# IDD_measurement.net
KiCad netlist of a schematic drawn in Altium Designer
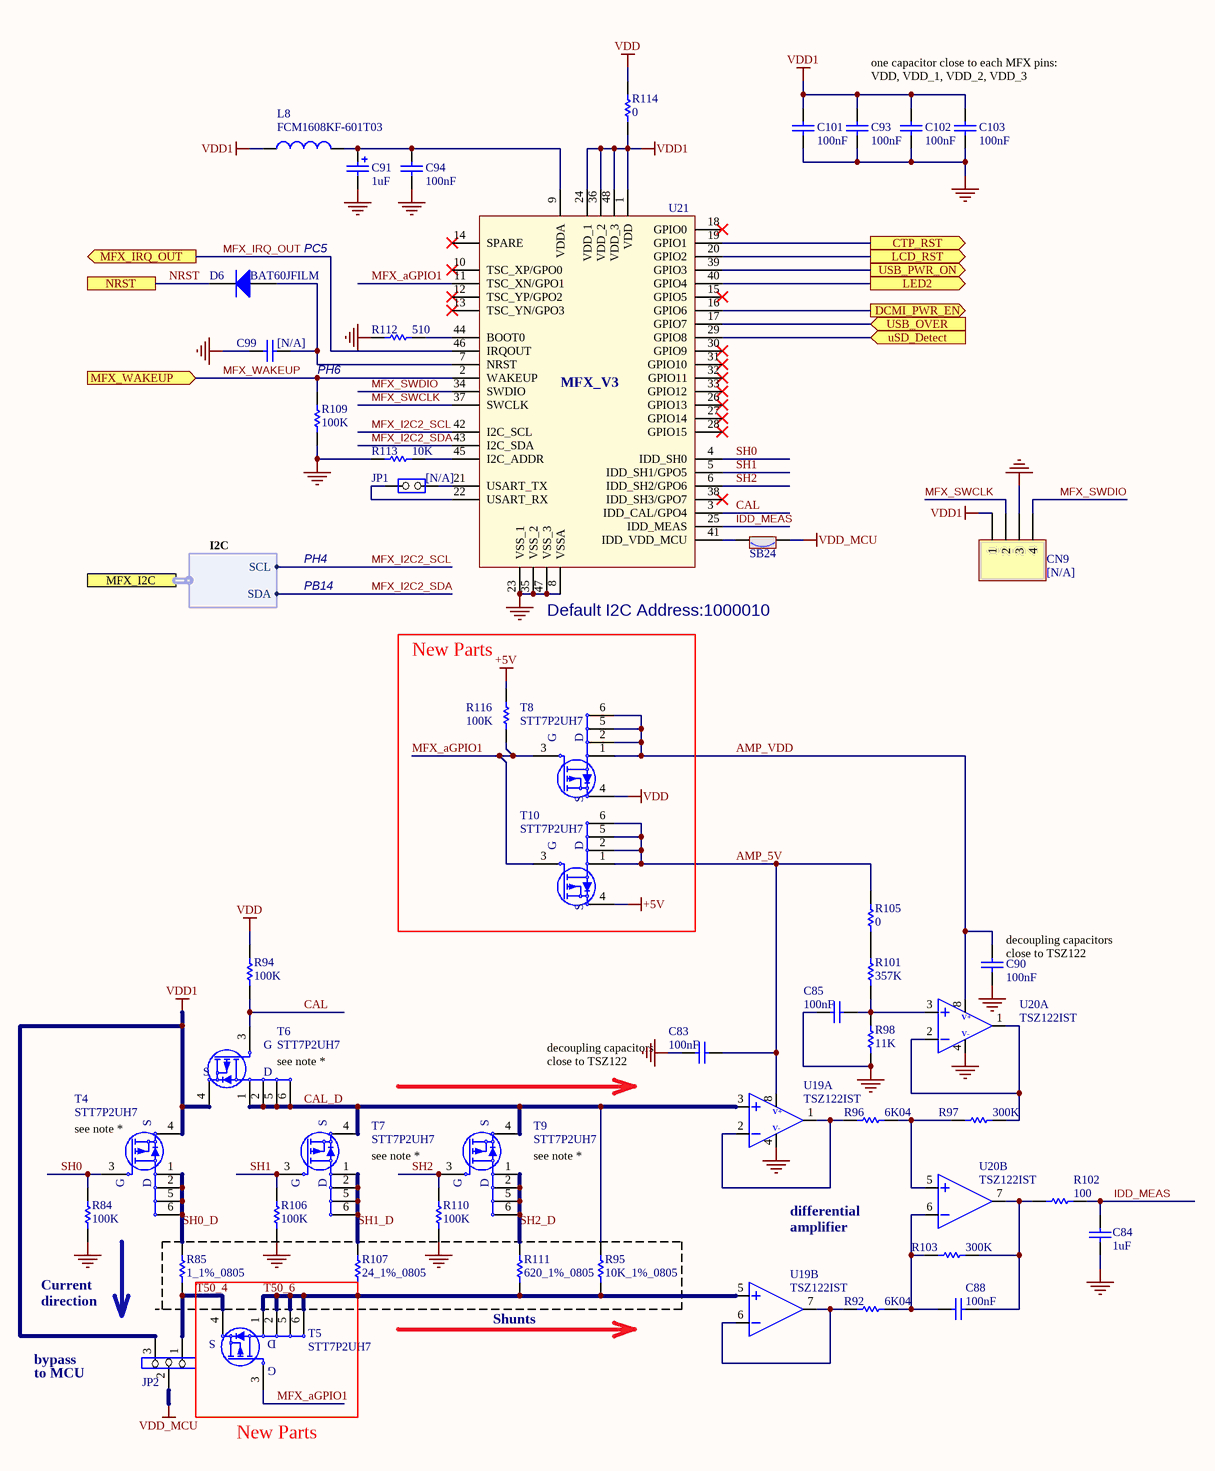
[diagram p0: IDD_measurement.SchDoc]

(export (version "E")
  (design (tool "Eeschema 10.0.6"))
  (components
    (comp (ref "C83")
      (value "100nF")
      (footprint "0603C")
      (description "Capacitor,100nF,10%,16V,X7R,0603,YAGEO")
      (fields (field (name "Comment") "CC0603KRX7R7BB104") (field (name "PUBLISHER") "Altium Limited"))
      (libsource (lib "Miscellaneous Devices") (part "Cap"))
    )
    (comp (ref "C84")
      (value "1uF")
      (footprint "0603C")
      (description "Capacitor,1uF,0603,16V,10%,X5R,YAGEO")
      (fields (field (name "Comment") "CC0603KRX5R7BB105") (field (name "PUBLISHER") "Altium Limited"))
      (libsource (lib "Miscellaneous Devices") (part "Cap"))
    )
    (comp (ref "C85")
      (value "100nF")
      (footprint "0603C")
      (description "Capacitor,100nF,10%,16V,X7R,0603,YAGEO")
      (fields (field (name "Comment") "CC0603KRX7R7BB104") (field (name "PUBLISHER") "Altium Limited"))
      (libsource (lib "Miscellaneous Devices") (part "Cap"))
    )
    (comp (ref "C88")
      (value "100nF")
      (footprint "0603C")
      (description "Capacitor,100nF,10%,16V,X7R,0603,YAGEO")
      (fields (field (name "Comment") "CC0603KRX7R7BB104") (field (name "PUBLISHER") "Altium Limited"))
      (libsource (lib "Miscellaneous Devices") (part "Cap"))
    )
    (comp (ref "C90")
      (value "100nF")
      (footprint "0603C")
      (description "Capacitor,100nF,10%,16V,X7R,0603,YAGEO")
      (fields (field (name "Comment") "CC0603KRX7R7BB104") (field (name "PUBLISHER") "Altium Limited"))
      (libsource (lib "Miscellaneous Devices") (part "Cap"))
    )
    (comp (ref "C91")
      (value "1uF")
      (footprint "TAN-A")
      (description "Tan Capacitor,1uF,10%,16V,Tan-A,TAJA105K016R")
      (fields (field (name "Comment") "TAJA105K016R") (field (name "PUBLISHER") "Altium Limited"))
      (libsource (lib "Miscellaneous Devices") (part "Cap Pol1"))
    )
    (comp (ref "C93")
      (value "100nF")
      (footprint "0603C")
      (description "Capacitor,100nF,10%,16V,X7R,0603,YAGEO")
      (fields (field (name "Comment") "CC0603KRX7R7BB104") (field (name "PUBLISHER") "Altium Limited"))
      (libsource (lib "Miscellaneous Devices") (part "Cap"))
    )
    (comp (ref "C94")
      (value "100nF")
      (footprint "0603C")
      (description "Capacitor,100nF,10%,16V,X7R,0603,YAGEO")
      (fields (field (name "Comment") "CC0603KRX7R7BB104") (field (name "PUBLISHER") "Altium Limited"))
      (libsource (lib "Miscellaneous Devices") (part "Cap"))
    )
    (comp (ref "C99")
      (value "[N/A]")
      (footprint "0603C")
      (description "Capacitor,100nF,10%,16V,X7R,0603,YAGEO")
      (fields (field (name "PUBLISHER") "Altium Limited"))
      (libsource (lib "Miscellaneous Devices") (part "Cap"))
    )
    (comp (ref "C101")
      (value "100nF")
      (footprint "0603C")
      (description "Capacitor,100nF,10%,16V,X7R,0603,YAGEO")
      (fields (field (name "Comment") "CC0603KRX7R7BB104") (field (name "PUBLISHER") "Altium Limited"))
      (libsource (lib "Miscellaneous Devices") (part "Cap"))
    )
    (comp (ref "C102")
      (value "100nF")
      (footprint "0603C")
      (description "Capacitor,100nF,10%,16V,X7R,0603,YAGEO")
      (fields (field (name "Comment") "CC0603KRX7R7BB104") (field (name "PUBLISHER") "Altium Limited"))
      (libsource (lib "Miscellaneous Devices") (part "Cap"))
    )
    (comp (ref "C103")
      (value "100nF")
      (footprint "0603C")
      (description "Capacitor,100nF,10%,16V,X7R,0603,YAGEO")
      (fields (field (name "Comment") "CC0603KRX7R7BB104") (field (name "PUBLISHER") "Altium Limited"))
      (libsource (lib "Miscellaneous Devices") (part "Cap"))
    )
    (comp (ref "CN9")
      (value "[N/A]")
      (footprint "HDR_1X4_2R54")
      (description "Header, 4-Pin")
      (fields (field (name "PUBLISHER") "Altium Limited"))
      (libsource (lib "MCD_TOOLS_CONNECTOR") (part "Header 4"))
    )
    (comp (ref "D6")
      (value "BAT60JFILM")
      (footprint "SOD-323")
      (fields (field (name "PROVIDED") "STM"))
      (libsource (lib "MCD_TOOLS") (part "BAT60JFILM"))
    )
    (comp (ref "JP1")
      (value "[N/A]")
      (footprint "SIP2")
      (description "2 PIN Jumper")
      (libsource (lib "*") (part "JP2"))
    )
    (comp (ref "JP2")
      (value "3 PIN Jumper")
      (footprint "SIP3")
      (description "Jumper 3 pins")
      (libsource (lib "MCD_TOOLS") (part "Jumper3"))
    )
    (comp (ref "L8")
      (value "FCM1608KF-601T03")
      (footprint "0603L")
      (description "Bead,600R,350mA,0603,FCM1608KF-601T03,Tai-tech")
      (libsource (lib "MCD_TOOLS") (part "BEAD_600R_350MA_0603"))
    )
    (comp (ref "R84")
      (value "100K")
      (footprint "0603R")
      (description "Resistor,100K,0603,1%,YAGEO")
      (fields (field (name "Comment") "RC0603FR-07100KL") (field (name "PUBLISHER") "Altium Limited"))
      (libsource (lib "Miscellaneous Devices") (part "res1"))
    )
    (comp (ref "R85")
      (value "1_1%_0805")
      (footprint "0805R")
      (description "Resistor,1,0805,1%,YAGEO")
      (libsource (lib "MCD_TOOLS") (part "Res_1_1%_0805"))
    )
    (comp (ref "R92")
      (value "6K04")
      (footprint "0603R")
      (description "Resistor,6.04K,0603,1%,YAGEO")
      (fields (field (name "Comment") "RC0603FR-076K04L") (field (name "PUBLISHER") "Altium Limited"))
      (libsource (lib "Miscellaneous Devices") (part "res1"))
    )
    (comp (ref "R94")
      (value "100K")
      (footprint "0603R")
      (description "Resistor,100K,0603,1%,YAGEO")
      (fields (field (name "Comment") "RC0603FR-07100KL") (field (name "PUBLISHER") "Altium Limited"))
      (libsource (lib "Miscellaneous Devices") (part "res1"))
    )
    (comp (ref "R95")
      (value "10K_1%_0805")
      (footprint "0805R")
      (description "Resistor,10K,0805,1%,YAGEO")
      (libsource (lib "MCD_TOOLS") (part "Res_10K_1%_0805"))
    )
    (comp (ref "R96")
      (value "6K04")
      (footprint "0603R")
      (description "Resistor,6.04K,0603,1%,YAGEO")
      (fields (field (name "Comment") "RC0603FR-076K04L") (field (name "PUBLISHER") "Altium Limited"))
      (libsource (lib "Miscellaneous Devices") (part "res1"))
    )
    (comp (ref "R97")
      (value "300K")
      (footprint "0603R")
      (description "Resistor,300K,0603,1%,YAGEO")
      (fields (field (name "Comment") "RC0603FR-07300KL") (field (name "PUBLISHER") "Altium Limited"))
      (libsource (lib "Miscellaneous Devices") (part "res1"))
    )
    (comp (ref "R98")
      (value "11K")
      (footprint "0603R")
      (description "Resistor,11K,0603,1%,YAGEO")
      (fields (field (name "Comment") "RC0603FR-0711KL") (field (name "PUBLISHER") "Altium Limited"))
      (libsource (lib "Miscellaneous Devices") (part "res1"))
    )
    (comp (ref "R101")
      (value "357K")
      (footprint "0603R")
      (description "Resistor,357K,0603,1%,YAGEO")
      (fields (field (name "Comment") "RC0603FR-07357KL") (field (name "PUBLISHER") "Altium Limited"))
      (libsource (lib "Miscellaneous Devices") (part "res1"))
    )
    (comp (ref "R102")
      (value "100")
      (footprint "0603R")
      (description "Resistor, 100 ,0603,1%,YAGEO")
      (fields (field (name "Comment") "RC0603JR-07100RL") (field (name "PUBLISHER") "Altium Limited"))
      (libsource (lib "Miscellaneous Devices") (part "res1"))
    )
    (comp (ref "R103")
      (value "300K")
      (footprint "0603R")
      (description "Resistor,300K,0603,1%,YAGEO")
      (fields (field (name "Comment") "RC0603FR-07300KL") (field (name "PUBLISHER") "Altium Limited"))
      (libsource (lib "Miscellaneous Devices") (part "res1"))
    )
    (comp (ref "R105")
      (value "0")
      (footprint "0603R")
      (description "Resistor, 0 ,0603,1%,YAGEO")
      (fields (field (name "Comment") "RC0603JR-070RL") (field (name "PUBLISHER") "Altium Limited"))
      (libsource (lib "Miscellaneous Devices") (part "res1"))
    )
    (comp (ref "R106")
      (value "100K")
      (footprint "0603R")
      (description "Resistor,100K,0603,1%,YAGEO")
      (fields (field (name "Comment") "RC0603FR-07100KL") (field (name "PUBLISHER") "Altium Limited"))
      (libsource (lib "Miscellaneous Devices") (part "res1"))
    )
    (comp (ref "R107")
      (value "24_1%_0805")
      (footprint "0805R")
      (description "Resistor,24,0805,1%,YAGEO")
      (libsource (lib "MCD_TOOLS") (part "Res_24_1%_0805"))
    )
    (comp (ref "R109")
      (value "100K")
      (footprint "0603R")
      (description "Resistor,100K,0603,1%,YAGEO")
      (fields (field (name "Comment") "RC0603FR-07100KL") (field (name "PUBLISHER") "Altium Limited"))
      (libsource (lib "Miscellaneous Devices") (part "res1"))
    )
    (comp (ref "R110")
      (value "100K")
      (footprint "0603R")
      (description "Resistor,100K,0603,1%,YAGEO")
      (fields (field (name "Comment") "RC0603FR-07100KL") (field (name "PUBLISHER") "Altium Limited"))
      (libsource (lib "Miscellaneous Devices") (part "res1"))
    )
    (comp (ref "R111")
      (value "620_1%_0805")
      (footprint "0805R")
      (description "Resistor,620,0805,1%,YAGEO")
      (libsource (lib "MCD_TOOLS") (part "Res_620_1%_0805"))
    )
    (comp (ref "R112")
      (value "510")
      (footprint "0603R")
      (description "Resistor,510R,0603,1%,YAGEO")
      (fields (field (name "Comment") "RC0603FR-07510RL") (field (name "PUBLISHER") "Altium Limited"))
      (libsource (lib "Miscellaneous Devices") (part "res1"))
    )
    (comp (ref "R113")
      (value "10K")
      (footprint "0603R")
      (description "Resistor,10K,0603,1%,YAGEO")
      (fields (field (name "Comment") "RC0603FR-0710KL") (field (name "PUBLISHER") "Altium Limited"))
      (libsource (lib "Miscellaneous Devices") (part "res1"))
    )
    (comp (ref "R114")
      (value "0")
      (footprint "0603R")
      (description "Resistor, 0 ,0603,1%,YAGEO")
      (fields (field (name "Comment") "RC0603JR-070RL") (field (name "PUBLISHER") "Altium Limited"))
      (libsource (lib "Miscellaneous Devices") (part "res1"))
    )
    (comp (ref "R116")
      (value "100K")
      (footprint "0603R")
      (description "Resistor,100K,0603,1%,YAGEO")
      (fields (field (name "Comment") "RC0603FR-07100KL") (field (name "PUBLISHER") "Altium Limited"))
      (libsource (lib "Miscellaneous Devices") (part "res1"))
    )
    (comp (ref "SB24")
      (value "Solder Bridge ON")
      (footprint "SB_0603")
      (libsource (lib "MCD_TOOLS") (part "SB_ON"))
    )
    (comp (ref "T4")
      (value "STT7P2UH7")
      (footprint "SOT23-6L")
      (description "STripFET VII DeepGATE Power MOSFET, P-CHANNEL 20 V, 0.0146, 7 A - SOT23-6L")
      (libsource (lib "MCD_TOOLS") (part "STT7P2UH7"))
    )
    (comp (ref "T5")
      (value "STT7P2UH7")
      (footprint "SOT23-6L")
      (description "STripFET VII DeepGATE Power MOSFET, P-CHANNEL 20 V, 0.0146, 7 A - SOT23-6L")
      (libsource (lib "MCD_TOOLS") (part "STT7P2UH7"))
    )
    (comp (ref "T6")
      (value "STT7P2UH7")
      (footprint "SOT23-6L")
      (description "STripFET VII DeepGATE Power MOSFET, P-CHANNEL 20 V, 0.0146, 7 A - SOT23-6L")
      (libsource (lib "MCD_TOOLS") (part "STT7P2UH7"))
    )
    (comp (ref "T7")
      (value "STT7P2UH7")
      (footprint "SOT23-6L")
      (description "STripFET VII DeepGATE Power MOSFET, P-CHANNEL 20 V, 0.0146, 7 A - SOT23-6L")
      (libsource (lib "MCD_TOOLS") (part "STT7P2UH7"))
    )
    (comp (ref "T8")
      (value "STT7P2UH7")
      (footprint "SOT23-6L")
      (description "STripFET VII DeepGATE Power MOSFET, P-CHANNEL 20 V, 0.0146, 7 A - SOT23-6L")
      (libsource (lib "MCD_TOOLS") (part "STT7P2UH7"))
    )
    (comp (ref "T9")
      (value "STT7P2UH7")
      (footprint "SOT23-6L")
      (description "STripFET VII DeepGATE Power MOSFET, P-CHANNEL 20 V, 0.0146, 7 A - SOT23-6L")
      (libsource (lib "MCD_TOOLS") (part "STT7P2UH7"))
    )
    (comp (ref "T10")
      (value "STT7P2UH7")
      (footprint "SOT23-6L")
      (description "STripFET VII DeepGATE Power MOSFET, P-CHANNEL 20 V, 0.0146, 7 A - SOT23-6L")
      (libsource (lib "MCD_TOOLS") (part "STT7P2UH7"))
    )
    (comp (ref "U19")
      (value "TSZ122IST")
      (footprint "miniSO8")
      (description "Very high accuracy (5 礦) zero drift 5 V dual OpAmp")
      (libsource (lib "MCD_TOOLS") (part "TSZ122IST"))
    )
    (comp (ref "U20")
      (value "TSZ122IST")
      (footprint "miniSO8")
      (description "Very high accuracy (5 礦) zero drift 5 V dual OpAmp")
      (libsource (lib "MCD_TOOLS") (part "TSZ122IST"))
    )
    (comp (ref "U21")
      (value "STM32L152CCT6")
      (footprint "LQFP48_0R5_9X9")
      (description "Multifunction expander")
      (libsource (lib "MB1167") (part "MFX"))
    )
  )
  (nets
    (net (code "2") (name "+5V") (class "Default")
      (node (ref "R116") (pin "2") (pinfunction "2_2") (pintype "passive"))
      (node (ref "T10") (pin "4") (pinfunction "S_4") (pintype "passive"))
    )
    (net (code "3") (name "/AMP_5V") (class "Default")
      (node (ref "C83") (pin "2") (pinfunction "2_2") (pintype "passive"))
      (node (ref "R105") (pin "2") (pinfunction "2_2") (pintype "passive"))
      (node (ref "T10") (pin "1") (pinfunction "S_1") (pintype "passive"))
      (node (ref "T10") (pin "2") (pinfunction "S_2") (pintype "passive"))
      (node (ref "T10") (pin "5") (pinfunction "D_5") (pintype "passive"))
      (node (ref "T10") (pin "6") (pinfunction "D_6") (pintype "passive"))
      (node (ref "U19") (pin "8") (pintype "passive"))
    )
    (net (code "4") (name "/AMP_VDD") (class "Default")
      (node (ref "C90") (pin "1") (pinfunction "1_1") (pintype "passive"))
      (node (ref "T8") (pin "1") (pinfunction "S_1") (pintype "passive"))
      (node (ref "T8") (pin "2") (pinfunction "S_2") (pintype "passive"))
      (node (ref "T8") (pin "5") (pinfunction "D_5") (pintype "passive"))
      (node (ref "T8") (pin "6") (pinfunction "D_6") (pintype "passive"))
      (node (ref "U20") (pin "8") (pintype "passive"))
    )
    (net (code "5") (name "/CAL") (class "Default")
      (node (ref "R94") (pin "1") (pinfunction "1_1") (pintype "passive"))
      (node (ref "T6") (pin "3") (pinfunction "G_3") (pintype "passive"))
      (node (ref "U21") (pin "3") (pinfunction "IDD_CAL/GPO4_3") (pintype "passive"))
    )
    (net (code "6") (name "/CAL_D") (class "Default")
      (node (ref "R95") (pin "2") (pinfunction "2_2") (pintype "passive"))
      (node (ref "T6") (pin "1") (pinfunction "S_1") (pintype "passive"))
      (node (ref "T6") (pin "2") (pinfunction "S_2") (pintype "passive"))
      (node (ref "T6") (pin "5") (pinfunction "D_5") (pintype "passive"))
      (node (ref "T6") (pin "6") (pinfunction "D_6") (pintype "passive"))
      (node (ref "T7") (pin "4") (pinfunction "S_4") (pintype "passive"))
      (node (ref "T9") (pin "4") (pinfunction "S_4") (pintype "passive"))
      (node (ref "U19") (pin "3") (pintype "passive"))
    )
    (net (code "7") (name "/CTP_RST") (class "Default")
      (node (ref "U21") (pin "19") (pinfunction "GPIO1_19") (pintype "passive"))
    )
    (net (code "8") (name "/DCMI_PWR_EN") (class "Default")
      (node (ref "U21") (pin "16") (pinfunction "GPIO6_16") (pintype "passive"))
    )
    (net (code "9") (name "/IDD_MEAS") (class "Default")
      (node (ref "C84") (pin "1") (pinfunction "1_1") (pintype "passive"))
      (node (ref "R102") (pin "1") (pinfunction "1_1") (pintype "passive"))
      (node (ref "U21") (pin "25") (pinfunction "IDD_MEAS_25") (pintype "passive"))
    )
    (net (code "10") (name "/LCD_RST") (class "Default")
      (node (ref "U21") (pin "20") (pinfunction "GPIO2_20") (pintype "passive"))
    )
    (net (code "11") (name "/LED2") (class "Default")
      (node (ref "U21") (pin "40") (pinfunction "GPIO4_40") (pintype "passive"))
    )
    (net (code "12") (name "/MFX_I2C2_SCL") (class "Default")
      (node (ref "U21") (pin "42") (pinfunction "I2C_SCL_42") (pintype "passive"))
    )
    (net (code "13") (name "/MFX_I2C2_SDA") (class "Default")
      (node (ref "U21") (pin "43") (pinfunction "I2C_SDA_43") (pintype "passive"))
    )
    (net (code "14") (name "/MFX_IRQ_OUT") (class "Default")
      (node (ref "U21") (pin "46") (pinfunction "IRQOUT_46") (pintype "passive"))
    )
    (net (code "15") (name "/MFX_SWCLK") (class "Default")
      (node (ref "CN9") (pin "2") (pinfunction "2_2") (pintype "passive"))
      (node (ref "U21") (pin "37") (pinfunction "SWCLK_37") (pintype "passive"))
    )
    (net (code "16") (name "/MFX_SWDIO") (class "Default")
      (node (ref "CN9") (pin "4") (pinfunction "4_4") (pintype "passive"))
      (node (ref "U21") (pin "34") (pinfunction "SWDIO_34") (pintype "passive"))
    )
    (net (code "17") (name "/MFX_WAKEUP") (class "Default")
      (node (ref "R109") (pin "2") (pinfunction "2_2") (pintype "passive"))
      (node (ref "U21") (pin "2") (pinfunction "WAKEUP_2") (pintype "passive"))
    )
    (net (code "18") (name "/MFX_aGPIO1") (class "Default")
      (node (ref "R116") (pin "1") (pinfunction "1_1") (pintype "passive"))
      (node (ref "T10") (pin "3") (pinfunction "G_3") (pintype "passive"))
      (node (ref "T5") (pin "3") (pinfunction "G_3") (pintype "passive"))
      (node (ref "T8") (pin "3") (pinfunction "G_3") (pintype "passive"))
      (node (ref "U21") (pin "11") (pinfunction "TSC_XN/GPO1_11") (pintype "passive"))
    )
    (net (code "19") (name "/NRST") (class "Default")
      (node (ref "D6") (pin "2") (pinfunction "K_2") (pintype "passive"))
    )
    (net (code "20") (name "/SH0") (class "Default")
      (node (ref "R84") (pin "2") (pinfunction "2_2") (pintype "passive"))
      (node (ref "T4") (pin "3") (pinfunction "G_3") (pintype "passive"))
      (node (ref "U21") (pin "4") (pinfunction "IDD_SH0_4") (pintype "passive"))
    )
    (net (code "21") (name "/SH0_D") (class "Default")
      (node (ref "R85") (pin "2") (pinfunction "2_2") (pintype "passive"))
      (node (ref "T4") (pin "1") (pinfunction "S_1") (pintype "passive"))
      (node (ref "T4") (pin "2") (pinfunction "S_2") (pintype "passive"))
      (node (ref "T4") (pin "5") (pinfunction "D_5") (pintype "passive"))
      (node (ref "T4") (pin "6") (pinfunction "D_6") (pintype "passive"))
    )
    (net (code "22") (name "/SH1") (class "Default")
      (node (ref "R106") (pin "2") (pinfunction "2_2") (pintype "passive"))
      (node (ref "T7") (pin "3") (pinfunction "G_3") (pintype "passive"))
      (node (ref "U21") (pin "5") (pinfunction "IDD_SH1/GPO5_5") (pintype "passive"))
    )
    (net (code "23") (name "/SH1_D") (class "Default")
      (node (ref "R107") (pin "2") (pinfunction "2_2") (pintype "passive"))
      (node (ref "T7") (pin "1") (pinfunction "S_1") (pintype "passive"))
      (node (ref "T7") (pin "2") (pinfunction "S_2") (pintype "passive"))
      (node (ref "T7") (pin "5") (pinfunction "D_5") (pintype "passive"))
      (node (ref "T7") (pin "6") (pinfunction "D_6") (pintype "passive"))
    )
    (net (code "24") (name "/SH2") (class "Default")
      (node (ref "R110") (pin "2") (pinfunction "2_2") (pintype "passive"))
      (node (ref "T9") (pin "3") (pinfunction "G_3") (pintype "passive"))
      (node (ref "U21") (pin "6") (pinfunction "IDD_SH2/GPO6_6") (pintype "passive"))
    )
    (net (code "25") (name "/SH2_D") (class "Default")
      (node (ref "R111") (pin "2") (pinfunction "2_2") (pintype "passive"))
      (node (ref "T9") (pin "1") (pinfunction "S_1") (pintype "passive"))
      (node (ref "T9") (pin "2") (pinfunction "S_2") (pintype "passive"))
      (node (ref "T9") (pin "5") (pinfunction "D_5") (pintype "passive"))
      (node (ref "T9") (pin "6") (pinfunction "D_6") (pintype "passive"))
    )
    (net (code "26") (name "/T50_4") (class "Default")
      (node (ref "JP2") (pin "1") (pintype "passive"))
      (node (ref "R85") (pin "1") (pinfunction "1_1") (pintype "passive"))
      (node (ref "T5") (pin "4") (pinfunction "S_4") (pintype "passive"))
    )
    (net (code "27") (name "/T50_6") (class "Default")
      (node (ref "R107") (pin "1") (pinfunction "1_1") (pintype "passive"))
      (node (ref "R111") (pin "1") (pinfunction "1_1") (pintype "passive"))
      (node (ref "R95") (pin "1") (pinfunction "1_1") (pintype "passive"))
      (node (ref "T5") (pin "1") (pinfunction "S_1") (pintype "passive"))
      (node (ref "T5") (pin "2") (pinfunction "S_2") (pintype "passive"))
      (node (ref "T5") (pin "5") (pinfunction "D_5") (pintype "passive"))
      (node (ref "T5") (pin "6") (pinfunction "D_6") (pintype "passive"))
      (node (ref "U19") (pin "5") (pintype "passive"))
    )
    (net (code "28") (name "/USB_OVER") (class "Default")
      (node (ref "U21") (pin "17") (pinfunction "GPIO7_17") (pintype "passive"))
    )
    (net (code "29") (name "/USB_PWR_ON") (class "Default")
      (node (ref "U21") (pin "39") (pinfunction "GPIO3_39") (pintype "passive"))
    )
    (net (code "30") (name "/uSD_Detect") (class "Default")
      (node (ref "U21") (pin "29") (pinfunction "GPIO8_29") (pintype "passive"))
    )
    (net (code "32") (name "GND") (class "Default")
      (node (ref "C101") (pin "2") (pinfunction "2_2") (pintype "passive"))
      (node (ref "C102") (pin "2") (pinfunction "2_2") (pintype "passive"))
      (node (ref "C103") (pin "2") (pinfunction "2_2") (pintype "passive"))
      (node (ref "C83") (pin "1") (pinfunction "1_1") (pintype "passive"))
      (node (ref "C84") (pin "2") (pinfunction "2_2") (pintype "passive"))
      (node (ref "C85") (pin "1") (pinfunction "1_1") (pintype "passive"))
      (node (ref "C90") (pin "2") (pinfunction "2_2") (pintype "passive"))
      (node (ref "C91") (pin "2") (pinfunction "2_2") (pintype "passive"))
      (node (ref "C93") (pin "2") (pinfunction "2_2") (pintype "passive"))
      (node (ref "C94") (pin "2") (pinfunction "2_2") (pintype "passive"))
      (node (ref "C99") (pin "1") (pinfunction "1_1") (pintype "passive"))
      (node (ref "CN9") (pin "3") (pinfunction "3_3") (pintype "passive"))
      (node (ref "R106") (pin "1") (pinfunction "1_1") (pintype "passive"))
      (node (ref "R109") (pin "1") (pinfunction "1_1") (pintype "passive"))
      (node (ref "R110") (pin "1") (pinfunction "1_1") (pintype "passive"))
      (node (ref "R112") (pin "2") (pinfunction "2_2") (pintype "passive"))
      (node (ref "R113") (pin "2") (pinfunction "2_2") (pintype "passive"))
      (node (ref "R84") (pin "1") (pinfunction "1_1") (pintype "passive"))
      (node (ref "R98") (pin "2") (pinfunction "2_2") (pintype "passive"))
      (node (ref "U19") (pin "4") (pintype "passive"))
      (node (ref "U20") (pin "4") (pintype "passive"))
      (node (ref "U21") (pin "23") (pinfunction "VSS_1_23") (pintype "passive"))
      (node (ref "U21") (pin "35") (pinfunction "VSS_2_35") (pintype "passive"))
      (node (ref "U21") (pin "47") (pinfunction "VSS_3_47") (pintype "passive"))
      (node (ref "U21") (pin "8") (pinfunction "VSSA_8") (pintype "passive"))
    )
    (net (code "33") (name "Net-(C85-Pad2)") (class "Default")
      (node (ref "C85") (pin "2") (pinfunction "2_2") (pintype "passive"))
      (node (ref "R101") (pin "2") (pinfunction "2_2") (pintype "passive"))
      (node (ref "R98") (pin "1") (pinfunction "1_1") (pintype "passive"))
      (node (ref "U20") (pin "3") (pintype "passive"))
    )
    (net (code "34") (name "Net-(C88-Pad1)") (class "Default")
      (node (ref "C88") (pin "1") (pinfunction "1_1") (pintype "passive"))
      (node (ref "R103") (pin "1") (pinfunction "1_1") (pintype "passive"))
      (node (ref "R92") (pin "1") (pinfunction "1_1") (pintype "passive"))
      (node (ref "U20") (pin "6") (pintype "passive"))
    )
    (net (code "35") (name "Net-(C88-Pad2)") (class "Default")
      (node (ref "C88") (pin "2") (pinfunction "2_2") (pintype "passive"))
      (node (ref "R102") (pin "2") (pinfunction "2_2") (pintype "passive"))
      (node (ref "R103") (pin "2") (pinfunction "2_2") (pintype "passive"))
      (node (ref "U20") (pin "7") (pintype "passive"))
    )
    (net (code "36") (name "Net-(D6-A)") (class "Default")
      (node (ref "C99") (pin "2") (pinfunction "2_2") (pintype "passive"))
      (node (ref "D6") (pin "1") (pinfunction "A_1") (pintype "passive"))
      (node (ref "U21") (pin "7") (pinfunction "NRST_7") (pintype "passive"))
    )
    (net (code "37") (name "Net-(JP1-COMMON)") (class "Default")
      (node (ref "JP1") (pin "1") (pinfunction "COMMON_1") (pintype "passive"))
      (node (ref "U21") (pin "22") (pinfunction "USART_RX_22") (pintype "passive"))
    )
    (net (code "38") (name "Net-(JP1-NO)") (class "Default")
      (node (ref "JP1") (pin "2") (pinfunction "NO_2") (pintype "passive"))
      (node (ref "U21") (pin "21") (pinfunction "USART_TX_21") (pintype "passive"))
    )
    (net (code "39") (name "Net-(R92-Pad2)") (class "Default")
      (node (ref "R92") (pin "2") (pinfunction "2_2") (pintype "passive"))
      (node (ref "U19") (pin "6") (pintype "passive"))
      (node (ref "U19") (pin "7") (pintype "passive"))
    )
    (net (code "40") (name "Net-(R96-Pad1)") (class "Default")
      (node (ref "R96") (pin "1") (pinfunction "1_1") (pintype "passive"))
      (node (ref "R97") (pin "1") (pinfunction "1_1") (pintype "passive"))
      (node (ref "U20") (pin "5") (pintype "passive"))
    )
    (net (code "41") (name "Net-(R96-Pad2)") (class "Default")
      (node (ref "R96") (pin "2") (pinfunction "2_2") (pintype "passive"))
      (node (ref "U19") (pin "1") (pintype "passive"))
      (node (ref "U19") (pin "2") (pintype "passive"))
    )
    (net (code "42") (name "Net-(R97-Pad2)") (class "Default")
      (node (ref "R97") (pin "2") (pinfunction "2_2") (pintype "passive"))
      (node (ref "U20") (pin "1") (pintype "passive"))
      (node (ref "U20") (pin "2") (pintype "passive"))
    )
    (net (code "43") (name "Net-(R101-Pad1)") (class "Default")
      (node (ref "R101") (pin "1") (pinfunction "1_1") (pintype "passive"))
      (node (ref "R105") (pin "1") (pinfunction "1_1") (pintype "passive"))
    )
    (net (code "44") (name "Net-(U21-BOOT0)") (class "Default")
      (node (ref "R112") (pin "1") (pinfunction "1_1") (pintype "passive"))
      (node (ref "U21") (pin "44") (pinfunction "BOOT0_44") (pintype "passive"))
    )
    (net (code "45") (name "Net-(U21-I2C_ADDR)") (class "Default")
      (node (ref "R113") (pin "1") (pinfunction "1_1") (pintype "passive"))
      (node (ref "U21") (pin "45") (pinfunction "I2C_ADDR_45") (pintype "passive"))
    )
    (net (code "46") (name "Net-(U21-IDD_VDD_MCU)") (class "Default")
      (node (ref "SB24") (pin "2") (pinfunction "2_2") (pintype "passive"))
      (node (ref "U21") (pin "41") (pinfunction "IDD_VDD_MCU_41") (pintype "passive"))
    )
    (net (code "47") (name "Net-(U21-VDDA)") (class "Default")
      (node (ref "C91") (pin "1") (pinfunction "1_1") (pintype "passive"))
      (node (ref "C94") (pin "1") (pinfunction "1_1") (pintype "passive"))
      (node (ref "L8") (pin "2") (pinfunction "2_2") (pintype "passive"))
      (node (ref "U21") (pin "9") (pinfunction "VDDA_9") (pintype "passive"))
    )
    (net (code "48") (name "VDD") (class "Default")
      (node (ref "R114") (pin "1") (pinfunction "1_1") (pintype "passive"))
      (node (ref "R94") (pin "2") (pinfunction "2_2") (pintype "passive"))
      (node (ref "T8") (pin "4") (pinfunction "S_4") (pintype "passive"))
    )
    (net (code "49") (name "VDD1") (class "Default")
      (node (ref "C101") (pin "1") (pinfunction "1_1") (pintype "passive"))
      (node (ref "C102") (pin "1") (pinfunction "1_1") (pintype "passive"))
      (node (ref "C103") (pin "1") (pinfunction "1_1") (pintype "passive"))
      (node (ref "C93") (pin "1") (pinfunction "1_1") (pintype "passive"))
      (node (ref "CN9") (pin "1") (pinfunction "1_1") (pintype "passive"))
      (node (ref "JP2") (pin "3") (pintype "passive"))
      (node (ref "L8") (pin "1") (pinfunction "1_1") (pintype "passive"))
      (node (ref "R114") (pin "2") (pinfunction "2_2") (pintype "passive"))
      (node (ref "T4") (pin "4") (pinfunction "S_4") (pintype "passive"))
      (node (ref "T6") (pin "4") (pinfunction "S_4") (pintype "passive"))
      (node (ref "U21") (pin "1") (pinfunction "VDD_1") (pintype "passive"))
      (node (ref "U21") (pin "24") (pinfunction "VDD_1_24") (pintype "passive"))
      (node (ref "U21") (pin "36") (pinfunction "VDD_2_36") (pintype "passive"))
      (node (ref "U21") (pin "48") (pinfunction "VDD_3_48") (pintype "passive"))
    )
    (net (code "50") (name "VDD_MCU") (class "Default")
      (node (ref "JP2") (pin "2") (pintype "passive"))
      (node (ref "SB24") (pin "1") (pinfunction "1_1") (pintype "passive"))
    )
    (net (code "51") (name "unconnected-(U21-GPIO0-Pad18)") (class "Default")
      (node (ref "U21") (pin "18") (pinfunction "GPIO0_18") (pintype "passive+no_connect"))
    )
    (net (code "52") (name "unconnected-(U21-GPIO5-Pad15)") (class "Default")
      (node (ref "U21") (pin "15") (pinfunction "GPIO5_15") (pintype "passive+no_connect"))
    )
    (net (code "53") (name "unconnected-(U21-GPIO9-Pad30)") (class "Default")
      (node (ref "U21") (pin "30") (pinfunction "GPIO9_30") (pintype "passive+no_connect"))
    )
    (net (code "54") (name "unconnected-(U21-GPIO10-Pad31)") (class "Default")
      (node (ref "U21") (pin "31") (pinfunction "GPIO10_31") (pintype "passive+no_connect"))
    )
    (net (code "55") (name "unconnected-(U21-GPIO11-Pad32)") (class "Default")
      (node (ref "U21") (pin "32") (pinfunction "GPIO11_32") (pintype "passive+no_connect"))
    )
    (net (code "56") (name "unconnected-(U21-GPIO12-Pad33)") (class "Default")
      (node (ref "U21") (pin "33") (pinfunction "GPIO12_33") (pintype "passive+no_connect"))
    )
    (net (code "57") (name "unconnected-(U21-GPIO13-Pad26)") (class "Default")
      (node (ref "U21") (pin "26") (pinfunction "GPIO13_26") (pintype "passive+no_connect"))
    )
    (net (code "58") (name "unconnected-(U21-GPIO14-Pad27)") (class "Default")
      (node (ref "U21") (pin "27") (pinfunction "GPIO14_27") (pintype "passive+no_connect"))
    )
    (net (code "59") (name "unconnected-(U21-GPIO15-Pad28)") (class "Default")
      (node (ref "U21") (pin "28") (pinfunction "GPIO15_28") (pintype "passive+no_connect"))
    )
    (net (code "60") (name "unconnected-(U21-IDD_SH3{slash}GPO7-Pad38)") (class "Default")
      (node (ref "U21") (pin "38") (pinfunction "IDD_SH3/GPO7_38") (pintype "passive+no_connect"))
    )
    (net (code "61") (name "unconnected-(U21-SPARE-Pad14)") (class "Default")
      (node (ref "U21") (pin "14") (pinfunction "SPARE_14") (pintype "passive+no_connect"))
    )
    (net (code "62") (name "unconnected-(U21-TSC_XP{slash}GPO0-Pad10)") (class "Default")
      (node (ref "U21") (pin "10") (pinfunction "TSC_XP/GPO0_10") (pintype "passive+no_connect"))
    )
    (net (code "63") (name "unconnected-(U21-TSC_YN{slash}GPO3-Pad13)") (class "Default")
      (node (ref "U21") (pin "13") (pinfunction "TSC_YN/GPO3_13") (pintype "passive+no_connect"))
    )
    (net (code "64") (name "unconnected-(U21-TSC_YP{slash}GPO2-Pad12)") (class "Default")
      (node (ref "U21") (pin "12") (pinfunction "TSC_YP/GPO2_12") (pintype "passive+no_connect"))
    )
  )
)
